# shutter.net
KiCad netlist of a schematic drawn in EAGLE
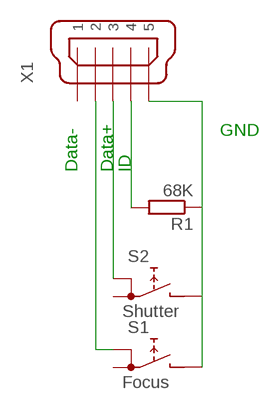
[diagram p0: schematic, sheet 1]

(export (version "E")
  (design (tool "Eeschema 10.0.6"))
  (components
    (comp (ref "R1")
      (value "68K")
      (footprint "eagle-import:0309_10")
      (libsource (lib "eagle-import") (part "R-EU_0309/10"))
    )
    (comp (ref "S1")
      (value "Focus")
      (footprint "eagle-import:RDT1034")
      (libsource (lib "eagle-import") (part "RDT1034"))
    )
    (comp (ref "S2")
      (value "Shutter")
      (footprint "eagle-import:RDT1034")
      (libsource (lib "eagle-import") (part "RDT1034"))
    )
    (comp (ref "X1")
      (value "MINI-USB-32005-301")
      (footprint "eagle-import:32005-301")
      (libsource (lib "eagle-import") (part "MINI-USB-32005-301"))
    )
  )
  (nets
    (net (code "1") (name "Net-(R1-Pad1)") (class "Default")
      (node (ref "R1") (pin "1") (pinfunction "1_1") (pintype "passive"))
      (node (ref "S1") (pin "B") (pinfunction "B_B") (pintype "passive"))
      (node (ref "S2") (pin "B") (pinfunction "B_B") (pintype "passive"))
      (node (ref "X1") (pin "5") (pinfunction "5_5") (pintype "passive"))
    )
    (net (code "2") (name "Net-(R1-Pad2)") (class "Default")
      (node (ref "R1") (pin "2") (pinfunction "2_2") (pintype "passive"))
      (node (ref "X1") (pin "4") (pinfunction "4_4") (pintype "passive"))
    )
    (net (code "3") (name "Net-(S1-PadA)") (class "Default")
      (node (ref "S1") (pin "A") (pinfunction "A_A") (pintype "passive"))
      (node (ref "X1") (pin "2") (pinfunction "2_2") (pintype "passive"))
    )
    (net (code "4") (name "Net-(S2-PadA)") (class "Default")
      (node (ref "S2") (pin "A") (pinfunction "A_A") (pintype "passive"))
      (node (ref "X1") (pin "3") (pinfunction "3_3") (pintype "passive"))
    )
    (net (code "5") (name "unconnected-(S1-PadA1)") (class "Default")
      (node (ref "S1") (pin "A1") (pinfunction "A1_A1") (pintype "passive"))
    )
    (net (code "6") (name "unconnected-(S2-PadA1)") (class "Default")
      (node (ref "S2") (pin "A1") (pinfunction "A1_A1") (pintype "passive"))
    )
    (net (code "7") (name "unconnected-(X1-Pad1)") (class "Default")
      (node (ref "X1") (pin "1") (pinfunction "1_1") (pintype "passive"))
    )
  )
)
